# HMS_Olfactometer_v2_0.net
KiCad netlist of a schematic drawn in EAGLE
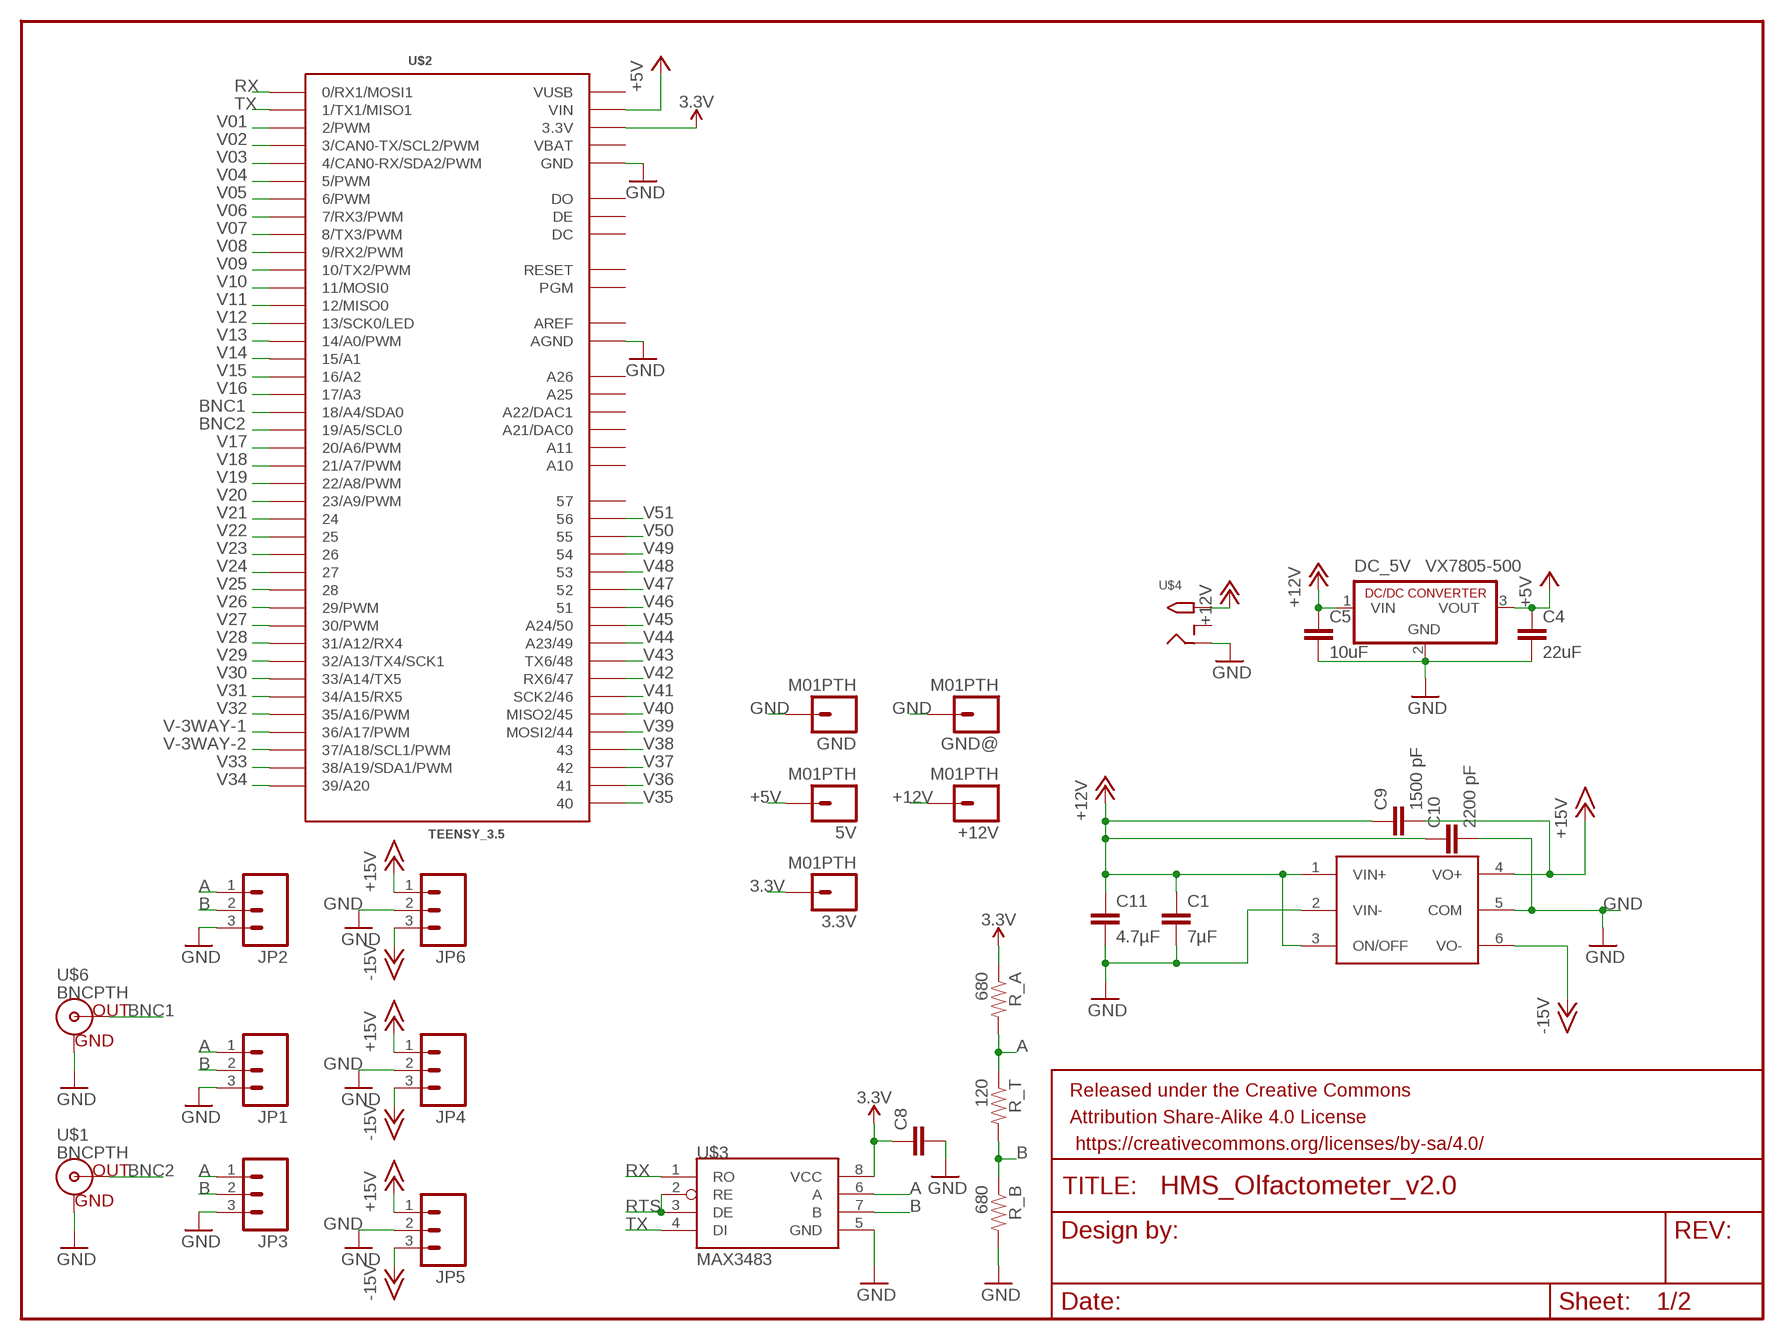
[diagram p0: schematic, sheet 1]
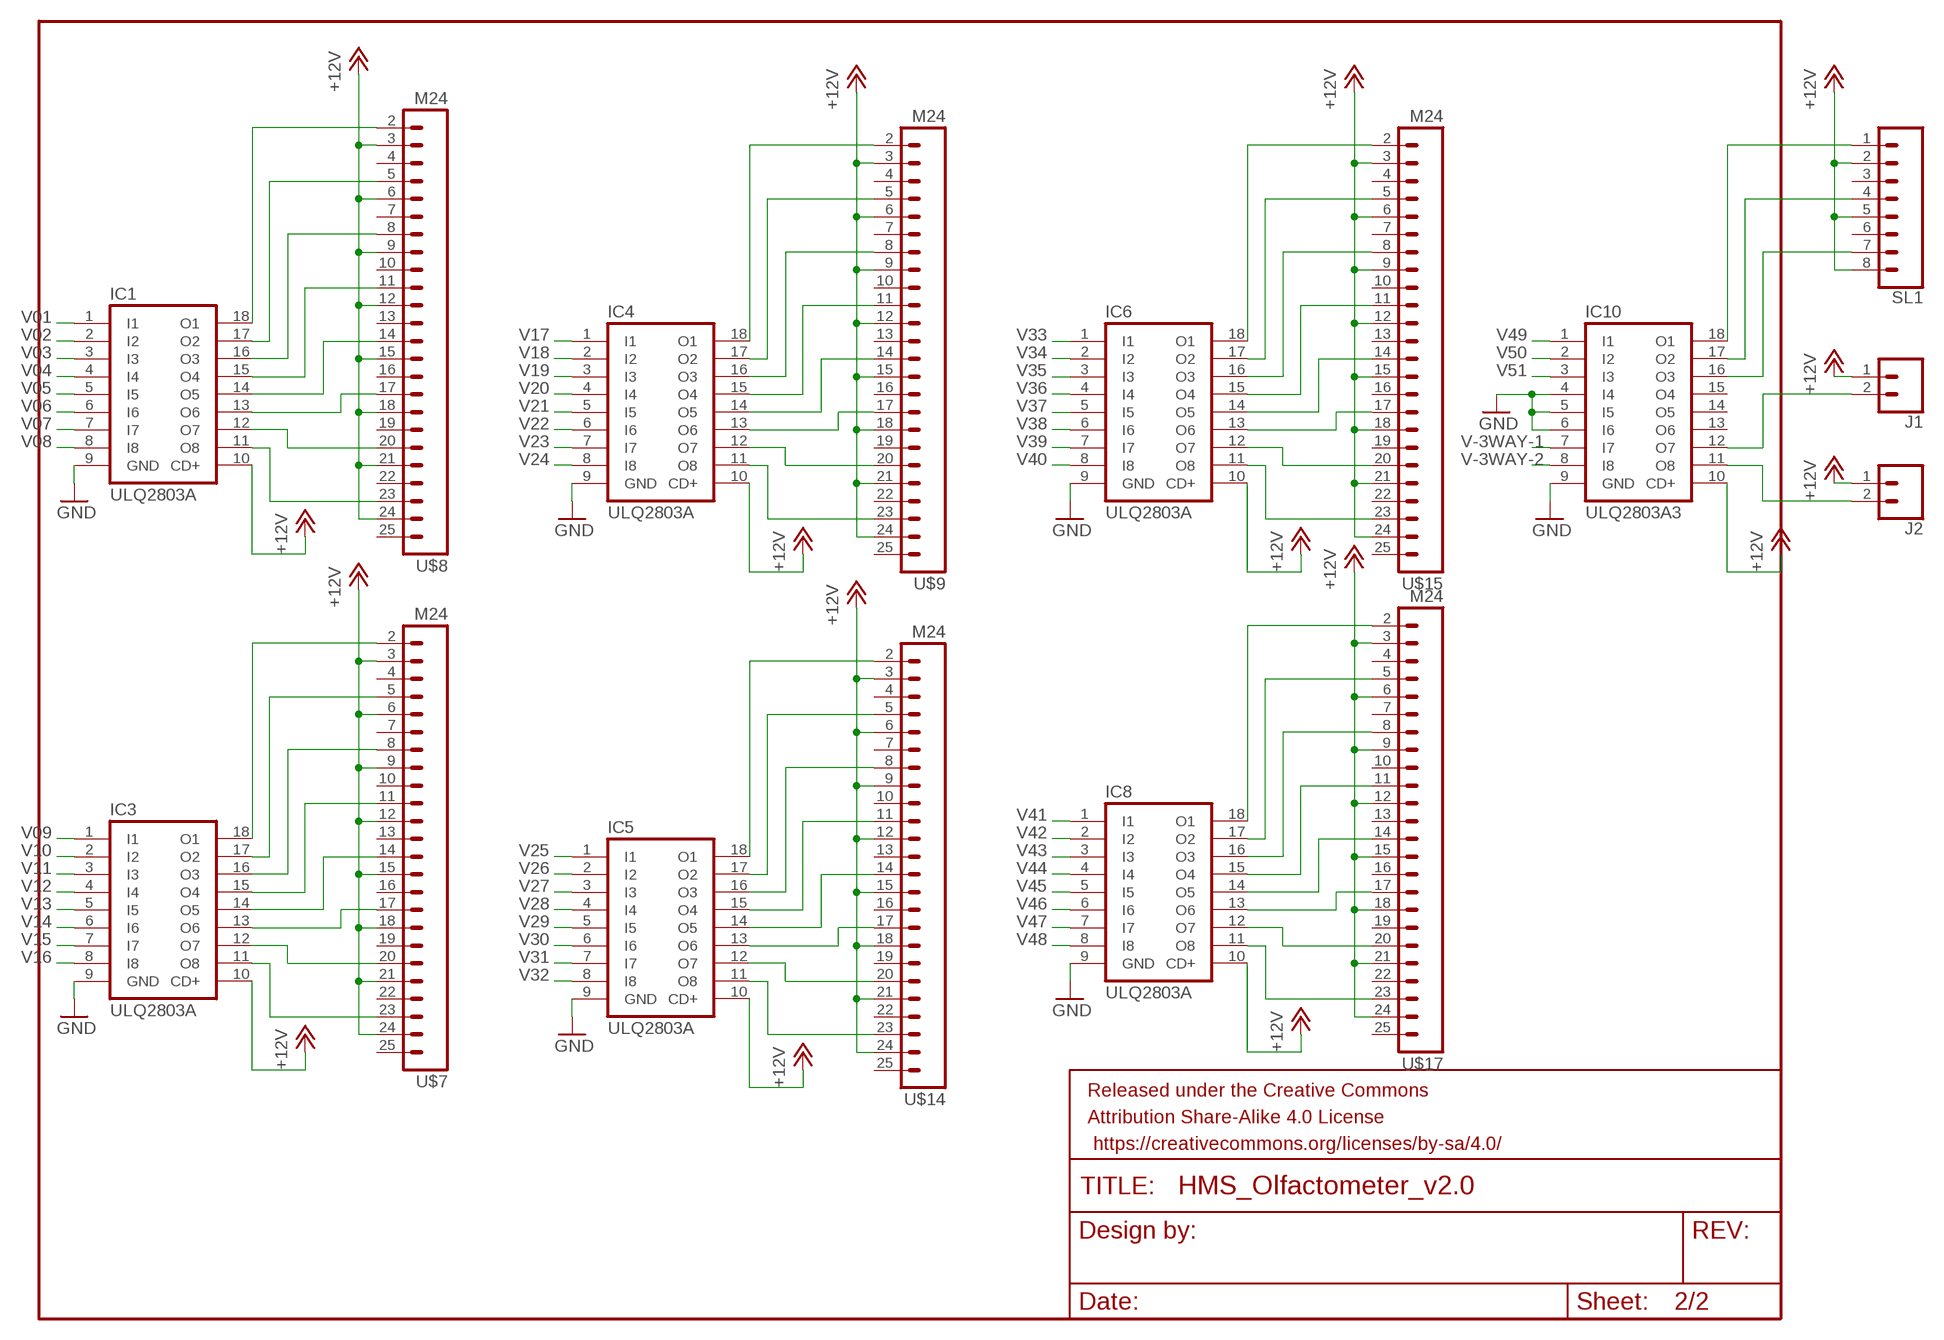
[diagram p1: schematic, sheet 2]

(export (version "E")
  (design (tool "Eeschema 10.0.6"))
  (components
    (comp (ref "+12V")
      (value "M01PTH")
      (footprint "eagle-import:1X01")
      (libsource (lib "eagle-import") (part "M01PTH"))
    )
    (comp (ref "3.3V")
      (value "M01PTH")
      (footprint "eagle-import:1X01")
      (libsource (lib "eagle-import") (part "M01PTH"))
    )
    (comp (ref "5V")
      (value "M01PTH")
      (footprint "eagle-import:1X01")
      (libsource (lib "eagle-import") (part "M01PTH"))
    )
    (comp (ref "C1")
      (value "7µF")
      (footprint "eagle-import:C1812")
      (libsource (lib "eagle-import") (part "C-EUC1812"))
    )
    (comp (ref "C4")
      (value "22uF")
      (footprint "eagle-import:1206")
      (libsource (lib "eagle-import") (part "10UF-6.3V-20%(1206)"))
    )
    (comp (ref "C5")
      (value "10uF")
      (footprint "eagle-import:1206")
      (libsource (lib "eagle-import") (part "CAP1206"))
    )
    (comp (ref "C8")
      (value "CAP1206")
      (footprint "eagle-import:1206")
      (libsource (lib "eagle-import") (part "CAP1206"))
    )
    (comp (ref "C9")
      (value "1500 pF")
      (footprint "eagle-import:C1206")
      (libsource (lib "eagle-import") (part "C-EUC1206"))
    )
    (comp (ref "C10")
      (value "2200 pF")
      (footprint "eagle-import:C1206")
      (libsource (lib "eagle-import") (part "C-EUC1206"))
    )
    (comp (ref "C11")
      (value "4.7µF")
      (footprint "eagle-import:C1812")
      (libsource (lib "eagle-import") (part "C-EUC1812"))
    )
    (comp (ref "DC_+/-15V")
      (value "XPPOWER_+/-15V_60W_DC-DC_SUPPLY")
      (footprint "eagle-import:XPPOWER_60W_JTL60_DC_DC_POWER_SUPPLY")
      (libsource (lib "eagle-import") (part "XPPOWER_+/-15V_60W_DC-DC_SUPPLY"))
    )
    (comp (ref "DC_5V")
      (value "VX7805-500")
      (footprint "eagle-import:SIP3")
      (libsource (lib "eagle-import") (part "R-78C-1.012"))
    )
    (comp (ref "FRAME1")
      (value "FRAME-LETTER")
      (footprint "eagle-import:CREATIVE_COMMONS")
      (libsource (lib "eagle-import") (part "FRAME-LETTER"))
    )
    (comp (ref "GND")
      (value "M01PTH")
      (footprint "eagle-import:1X01")
      (libsource (lib "eagle-import") (part "M01PTH"))
    )
    (comp (ref "GND@")
      (value "M01PTH")
      (footprint "eagle-import:1X01")
      (libsource (lib "eagle-import") (part "M01PTH"))
    )
    (comp (ref "JP1")
      (value "M03POLAR")
      (footprint "eagle-import:MOLEX-1X3")
      (libsource (lib "eagle-import") (part "M03POLAR"))
    )
    (comp (ref "JP2")
      (value "M03POLAR")
      (footprint "eagle-import:MOLEX-1X3")
      (libsource (lib "eagle-import") (part "M03POLAR"))
    )
    (comp (ref "JP3")
      (value "M03POLAR")
      (footprint "eagle-import:MOLEX-1X3")
      (libsource (lib "eagle-import") (part "M03POLAR"))
    )
    (comp (ref "JP4")
      (value "M03SCREW")
      (footprint "eagle-import:SCREWTERMINAL-3.5MM-3")
      (libsource (lib "eagle-import") (part "M03SCREW"))
    )
    (comp (ref "JP5")
      (value "M03SCREW")
      (footprint "eagle-import:SCREWTERMINAL-3.5MM-3")
      (libsource (lib "eagle-import") (part "M03SCREW"))
    )
    (comp (ref "JP6")
      (value "M03SCREW")
      (footprint "eagle-import:SCREWTERMINAL-3.5MM-3")
      (libsource (lib "eagle-import") (part "M03SCREW"))
    )
    (comp (ref "R_A")
      (value "680")
      (footprint "eagle-import:AXIAL-0.5")
      (libsource (lib "eagle-import") (part "RESISTORPTH-1/2W"))
    )
    (comp (ref "R_B")
      (value "680")
      (footprint "eagle-import:AXIAL-0.5")
      (libsource (lib "eagle-import") (part "RESISTORPTH-1/2W"))
    )
    (comp (ref "R_T")
      (value "120")
      (footprint "eagle-import:AXIAL-0.5")
      (libsource (lib "eagle-import") (part "RESISTORPTH-1/2W"))
    )
    (comp (ref "U$1")
      (value "BNCPTH")
      (footprint "eagle-import:BNC")
      (libsource (lib "eagle-import") (part "BNCPTH"))
    )
    (comp (ref "U$2")
      (value "TEENSY_3.5")
      (footprint "eagle-import:TEENSY_3.5_ALL_PINS&PADS")
      (libsource (lib "eagle-import") (part "TEENSY_3.5_ALL_PINS&PADS"))
    )
    (comp (ref "U$3")
      (value "MAX3483")
      (footprint "eagle-import:DIL08")
      (fields (field (name "SPICEPREFIX") "X"))
      (libsource (lib "eagle-import") (part "MAX485DIL"))
    )
    (comp (ref "U$4")
      (value "2.1MMJACKTHM")
      (footprint "eagle-import:PJ-102A")
      (libsource (lib "eagle-import") (part "2.1MMJACKTHM"))
    )
    (comp (ref "U$6")
      (value "BNCPTH")
      (footprint "eagle-import:BNC")
      (libsource (lib "eagle-import") (part "BNCPTH"))
    )
    (comp (ref "FRAME2")
      (value "FRAME-LETTER")
      (footprint "eagle-import:CREATIVE_COMMONS")
      (libsource (lib "eagle-import") (part "FRAME-LETTER"))
    )
    (comp (ref "IC1")
      (value "ULQ2803A")
      (footprint "eagle-import:DIL18")
      (libsource (lib "eagle-import") (part "ULN2803A"))
    )
    (comp (ref "IC3")
      (value "ULQ2803A")
      (footprint "eagle-import:DIL18")
      (libsource (lib "eagle-import") (part "ULN2803A"))
    )
    (comp (ref "IC4")
      (value "ULQ2803A")
      (footprint "eagle-import:DIL18")
      (libsource (lib "eagle-import") (part "ULN2803A"))
    )
    (comp (ref "IC5")
      (value "ULQ2803A")
      (footprint "eagle-import:DIL18")
      (libsource (lib "eagle-import") (part "ULN2803A"))
    )
    (comp (ref "IC6")
      (value "ULQ2803A")
      (footprint "eagle-import:DIL18")
      (libsource (lib "eagle-import") (part "ULN2803A"))
    )
    (comp (ref "IC8")
      (value "ULQ2803A")
      (footprint "eagle-import:DIL18")
      (libsource (lib "eagle-import") (part "ULN2803A"))
    )
    (comp (ref "IC10")
      (value "ULQ2803A3")
      (footprint "eagle-import:DIL18")
      (libsource (lib "eagle-import") (part "ULN2803A"))
    )
    (comp (ref "J1")
      (value "CONN_02")
      (footprint "eagle-import:1X02")
      (libsource (lib "eagle-import") (part "CONN_02"))
    )
    (comp (ref "J2")
      (value "CONN_02")
      (footprint "eagle-import:1X02")
      (libsource (lib "eagle-import") (part "CONN_02"))
    )
    (comp (ref "SL1")
      (value "CONN_08\"")
      (footprint "eagle-import:1X08")
      (libsource (lib "eagle-import") (part "CONN_08{dblquote}"))
    )
    (comp (ref "U$7")
      (value "M24")
      (footprint "eagle-import:1X24")
      (libsource (lib "eagle-import") (part "M24"))
    )
    (comp (ref "U$8")
      (value "M24")
      (footprint "eagle-import:1X24")
      (libsource (lib "eagle-import") (part "M24"))
    )
    (comp (ref "U$9")
      (value "M24")
      (footprint "eagle-import:1X24")
      (libsource (lib "eagle-import") (part "M24"))
    )
    (comp (ref "U$14")
      (value "M24")
      (footprint "eagle-import:1X24")
      (libsource (lib "eagle-import") (part "M24"))
    )
    (comp (ref "U$15")
      (value "M24")
      (footprint "eagle-import:1X24")
      (libsource (lib "eagle-import") (part "M24"))
    )
    (comp (ref "U$17")
      (value "M24")
      (footprint "eagle-import:1X24")
      (libsource (lib "eagle-import") (part "M24"))
    )
  )
  (nets
    (net (code "1") (name "+5V") (class "Default")
      (node (ref "5V") (pin "1") (pinfunction "1_1") (pintype "passive"))
      (node (ref "C4") (pin "1") (pinfunction "1_1") (pintype "passive"))
      (node (ref "DC_5V") (pin "3") (pinfunction "VOUT_3") (pintype "passive"))
      (node (ref "U$2") (pin "VIN") (pinfunction "VIN_VIN") (pintype "power_in"))
    )
    (net (code "2") (name "+12V") (class "Default")
      (node (ref "+12V") (pin "1") (pinfunction "1_1") (pintype "passive"))
      (node (ref "C1") (pin "1") (pinfunction "1_1") (pintype "passive"))
      (node (ref "C10") (pin "1") (pinfunction "1_1") (pintype "passive"))
      (node (ref "C11") (pin "1") (pinfunction "1_1") (pintype "passive"))
      (node (ref "C5") (pin "1") (pinfunction "1_1") (pintype "passive"))
      (node (ref "C9") (pin "1") (pinfunction "1_1") (pintype "passive"))
      (node (ref "DC_+/-15V") (pin "1") (pinfunction "VIN+_1") (pintype "passive"))
      (node (ref "DC_+/-15V") (pin "3") (pinfunction "ON/OFF_3") (pintype "bidirectional"))
      (node (ref "DC_5V") (pin "1") (pinfunction "VIN_1") (pintype "passive"))
      (node (ref "IC1") (pin "10") (pinfunction "CD+_10") (pintype "passive"))
      (node (ref "IC10") (pin "10") (pinfunction "CD+_10") (pintype "passive"))
      (node (ref "IC3") (pin "10") (pinfunction "CD+_10") (pintype "passive"))
      (node (ref "IC4") (pin "10") (pinfunction "CD+_10") (pintype "passive"))
      (node (ref "IC5") (pin "10") (pinfunction "CD+_10") (pintype "passive"))
      (node (ref "IC6") (pin "10") (pinfunction "CD+_10") (pintype "passive"))
      (node (ref "IC8") (pin "10") (pinfunction "CD+_10") (pintype "passive"))
      (node (ref "J1") (pin "1") (pinfunction "1_1") (pintype "passive"))
      (node (ref "J2") (pin "1") (pinfunction "1_1") (pintype "passive"))
      (node (ref "SL1") (pin "2") (pinfunction "2_2") (pintype "passive"))
      (node (ref "SL1") (pin "5") (pinfunction "5_5") (pintype "passive"))
      (node (ref "SL1") (pin "8") (pinfunction "8_8") (pintype "passive"))
      (node (ref "U$14") (pin "12") (pinfunction "12_12") (pintype "passive"))
      (node (ref "U$14") (pin "15") (pinfunction "15_15") (pintype "passive"))
      (node (ref "U$14") (pin "18") (pinfunction "18_18") (pintype "passive"))
      (node (ref "U$14") (pin "21") (pinfunction "21_21") (pintype "passive"))
      (node (ref "U$14") (pin "24") (pinfunction "24_24") (pintype "passive"))
      (node (ref "U$14") (pin "3") (pinfunction "3_3") (pintype "passive"))
      (node (ref "U$14") (pin "6") (pinfunction "6_6") (pintype "passive"))
      (node (ref "U$14") (pin "9") (pinfunction "9_9") (pintype "passive"))
      (node (ref "U$15") (pin "12") (pinfunction "12_12") (pintype "passive"))
      (node (ref "U$15") (pin "15") (pinfunction "15_15") (pintype "passive"))
      (node (ref "U$15") (pin "18") (pinfunction "18_18") (pintype "passive"))
      (node (ref "U$15") (pin "21") (pinfunction "21_21") (pintype "passive"))
      (node (ref "U$15") (pin "24") (pinfunction "24_24") (pintype "passive"))
      (node (ref "U$15") (pin "3") (pinfunction "3_3") (pintype "passive"))
      (node (ref "U$15") (pin "6") (pinfunction "6_6") (pintype "passive"))
      (node (ref "U$15") (pin "9") (pinfunction "9_9") (pintype "passive"))
      (node (ref "U$17") (pin "12") (pinfunction "12_12") (pintype "passive"))
      (node (ref "U$17") (pin "15") (pinfunction "15_15") (pintype "passive"))
      (node (ref "U$17") (pin "18") (pinfunction "18_18") (pintype "passive"))
      (node (ref "U$17") (pin "21") (pinfunction "21_21") (pintype "passive"))
      (node (ref "U$17") (pin "24") (pinfunction "24_24") (pintype "passive"))
      (node (ref "U$17") (pin "3") (pinfunction "3_3") (pintype "passive"))
      (node (ref "U$17") (pin "6") (pinfunction "6_6") (pintype "passive"))
      (node (ref "U$17") (pin "9") (pinfunction "9_9") (pintype "passive"))
      (node (ref "U$4") (pin "TIP") (pinfunction "TIP_TIP") (pintype "bidirectional"))
      (node (ref "U$7") (pin "12") (pinfunction "12_12") (pintype "passive"))
      (node (ref "U$7") (pin "15") (pinfunction "15_15") (pintype "passive"))
      (node (ref "U$7") (pin "18") (pinfunction "18_18") (pintype "passive"))
      (node (ref "U$7") (pin "21") (pinfunction "21_21") (pintype "passive"))
      (node (ref "U$7") (pin "24") (pinfunction "24_24") (pintype "passive"))
      (node (ref "U$7") (pin "3") (pinfunction "3_3") (pintype "passive"))
      (node (ref "U$7") (pin "6") (pinfunction "6_6") (pintype "passive"))
      (node (ref "U$7") (pin "9") (pinfunction "9_9") (pintype "passive"))
      (node (ref "U$8") (pin "12") (pinfunction "12_12") (pintype "passive"))
      (node (ref "U$8") (pin "15") (pinfunction "15_15") (pintype "passive"))
      (node (ref "U$8") (pin "18") (pinfunction "18_18") (pintype "passive"))
      (node (ref "U$8") (pin "21") (pinfunction "21_21") (pintype "passive"))
      (node (ref "U$8") (pin "24") (pinfunction "24_24") (pintype "passive"))
      (node (ref "U$8") (pin "3") (pinfunction "3_3") (pintype "passive"))
      (node (ref "U$8") (pin "6") (pinfunction "6_6") (pintype "passive"))
      (node (ref "U$8") (pin "9") (pinfunction "9_9") (pintype "passive"))
      (node (ref "U$9") (pin "12") (pinfunction "12_12") (pintype "passive"))
      (node (ref "U$9") (pin "15") (pinfunction "15_15") (pintype "passive"))
      (node (ref "U$9") (pin "18") (pinfunction "18_18") (pintype "passive"))
      (node (ref "U$9") (pin "21") (pinfunction "21_21") (pintype "passive"))
      (node (ref "U$9") (pin "24") (pinfunction "24_24") (pintype "passive"))
      (node (ref "U$9") (pin "3") (pinfunction "3_3") (pintype "passive"))
      (node (ref "U$9") (pin "6") (pinfunction "6_6") (pintype "passive"))
      (node (ref "U$9") (pin "9") (pinfunction "9_9") (pintype "passive"))
    )
    (net (code "3") (name "+15V") (class "Default")
      (node (ref "C9") (pin "2") (pinfunction "2_2") (pintype "passive"))
      (node (ref "DC_+/-15V") (pin "4") (pinfunction "VO+_4") (pintype "power_in"))
      (node (ref "JP4") (pin "1") (pinfunction "1_1") (pintype "passive"))
      (node (ref "JP5") (pin "1") (pinfunction "1_1") (pintype "passive"))
      (node (ref "JP6") (pin "1") (pinfunction "1_1") (pintype "passive"))
    )
    (net (code "4") (name "-15V") (class "Default")
      (node (ref "DC_+/-15V") (pin "6") (pinfunction "VO-_6") (pintype "power_in"))
      (node (ref "JP4") (pin "3") (pinfunction "3_3") (pintype "passive"))
      (node (ref "JP5") (pin "3") (pinfunction "3_3") (pintype "passive"))
      (node (ref "JP6") (pin "3") (pinfunction "3_3") (pintype "passive"))
    )
    (net (code "5") (name "3.3V") (class "Default")
      (node (ref "3.3V") (pin "1") (pinfunction "1_1") (pintype "passive"))
      (node (ref "C8") (pin "1") (pinfunction "1_1") (pintype "passive"))
      (node (ref "R_A") (pin "P$1") (pinfunction "1_P$1") (pintype "passive"))
      (node (ref "U$2") (pin "3.3V") (pinfunction "3.3V_3.3V") (pintype "power_in"))
      (node (ref "U$2") (pin "3.3V2") (pinfunction "3.3V_3.3V2") (pintype "power_in"))
      (node (ref "U$2") (pin "3.3V3") (pinfunction "3.3V_3.3V3") (pintype "power_in"))
      (node (ref "U$2") (pin "3.3V4") (pinfunction "3.3V_3.3V4") (pintype "power_in"))
      (node (ref "U$3") (pin "8") (pinfunction "VCC_8") (pintype "bidirectional"))
    )
    (net (code "6") (name "A") (class "Default")
      (node (ref "JP1") (pin "1") (pinfunction "1_1") (pintype "passive"))
      (node (ref "JP2") (pin "1") (pinfunction "1_1") (pintype "passive"))
      (node (ref "JP3") (pin "1") (pinfunction "1_1") (pintype "passive"))
      (node (ref "R_A") (pin "P$2") (pinfunction "2_P$2") (pintype "passive"))
      (node (ref "R_T") (pin "P$1") (pinfunction "1_P$1") (pintype "passive"))
      (node (ref "U$3") (pin "6") (pinfunction "A_6") (pintype "bidirectional"))
    )
    (net (code "7") (name "AREF") (class "Default")
      (node (ref "U$2") (pin "AREF") (pinfunction "AREF_AREF") (pintype "power_in"))
    )
    (net (code "8") (name "B") (class "Default")
      (node (ref "JP1") (pin "2") (pinfunction "2_2") (pintype "passive"))
      (node (ref "JP2") (pin "2") (pinfunction "2_2") (pintype "passive"))
      (node (ref "JP3") (pin "2") (pinfunction "2_2") (pintype "passive"))
      (node (ref "R_B") (pin "P$1") (pinfunction "1_P$1") (pintype "passive"))
      (node (ref "R_T") (pin "P$2") (pinfunction "2_P$2") (pintype "passive"))
      (node (ref "U$3") (pin "7") (pinfunction "B_7") (pintype "bidirectional"))
    )
    (net (code "9") (name "BNC1") (class "Default")
      (node (ref "U$2") (pin "18/A4") (pinfunction "18/A4/SDA0_18/A4") (pintype "bidirectional"))
      (node (ref "U$6") (pin "S") (pinfunction "OUT_S") (pintype "bidirectional"))
    )
    (net (code "10") (name "BNC2") (class "Default")
      (node (ref "U$1") (pin "S") (pinfunction "OUT_S") (pintype "bidirectional"))
      (node (ref "U$2") (pin "19/A5") (pinfunction "19/A5/SCL0_19/A5") (pintype "bidirectional"))
    )
    (net (code "11") (name "GND") (class "Default")
      (node (ref "C1") (pin "2") (pinfunction "2_2") (pintype "passive"))
      (node (ref "C10") (pin "2") (pinfunction "2_2") (pintype "passive"))
      (node (ref "C11") (pin "2") (pinfunction "2_2") (pintype "passive"))
      (node (ref "C4") (pin "2") (pinfunction "2_2") (pintype "passive"))
      (node (ref "C5") (pin "2") (pinfunction "2_2") (pintype "passive"))
      (node (ref "C8") (pin "2") (pinfunction "2_2") (pintype "passive"))
      (node (ref "DC_+/-15V") (pin "2") (pinfunction "VIN-_2") (pintype "power_in"))
      (node (ref "DC_+/-15V") (pin "5") (pinfunction "COM_5") (pintype "power_in"))
      (node (ref "DC_5V") (pin "2") (pinfunction "GND_2") (pintype "passive"))
      (node (ref "GND") (pin "1") (pinfunction "1_1") (pintype "passive"))
      (node (ref "GND@") (pin "1") (pinfunction "1_1") (pintype "passive"))
      (node (ref "IC1") (pin "9") (pinfunction "GND_9") (pintype "power_in"))
      (node (ref "IC10") (pin "4") (pinfunction "I4_4") (pintype "input"))
      (node (ref "IC10") (pin "5") (pinfunction "I5_5") (pintype "input"))
      (node (ref "IC10") (pin "6") (pinfunction "I6_6") (pintype "input"))
      (node (ref "IC10") (pin "9") (pinfunction "GND_9") (pintype "power_in"))
      (node (ref "IC3") (pin "9") (pinfunction "GND_9") (pintype "power_in"))
      (node (ref "IC4") (pin "9") (pinfunction "GND_9") (pintype "power_in"))
      (node (ref "IC5") (pin "9") (pinfunction "GND_9") (pintype "power_in"))
      (node (ref "IC6") (pin "9") (pinfunction "GND_9") (pintype "power_in"))
      (node (ref "IC8") (pin "9") (pinfunction "GND_9") (pintype "power_in"))
      (node (ref "JP1") (pin "3") (pinfunction "3_3") (pintype "passive"))
      (node (ref "JP2") (pin "3") (pinfunction "3_3") (pintype "passive"))
      (node (ref "JP3") (pin "3") (pinfunction "3_3") (pintype "passive"))
      (node (ref "JP4") (pin "2") (pinfunction "2_2") (pintype "passive"))
      (node (ref "JP5") (pin "2") (pinfunction "2_2") (pintype "passive"))
      (node (ref "JP6") (pin "2") (pinfunction "2_2") (pintype "passive"))
      (node (ref "R_B") (pin "P$2") (pinfunction "2_P$2") (pintype "passive"))
      (node (ref "U$1") (pin "GND") (pinfunction "GND_GND") (pintype "bidirectional"))
      (node (ref "U$2") (pin "AGND") (pinfunction "AGND_AGND") (pintype "power_in"))
      (node (ref "U$2") (pin "GND") (pinfunction "GND_GND") (pintype "power_in"))
      (node (ref "U$2") (pin "GND1") (pinfunction "GND_GND1") (pintype "power_in"))
      (node (ref "U$2") (pin "GND2") (pinfunction "GND_GND2") (pintype "power_in"))
      (node (ref "U$2") (pin "GND3") (pinfunction "GND_GND3") (pintype "power_in"))
      (node (ref "U$2") (pin "GND4") (pinfunction "GND_GND4") (pintype "power_in"))
      (node (ref "U$2") (pin "GND5") (pinfunction "GND_GND5") (pintype "power_in"))
      (node (ref "U$2") (pin "GND6") (pinfunction "GND_GND6") (pintype "power_in"))
      (node (ref "U$3") (pin "5") (pinfunction "GND_5") (pintype "bidirectional"))
      (node (ref "U$4") (pin "RING") (pinfunction "RING_RING") (pintype "bidirectional"))
      (node (ref "U$6") (pin "GND") (pinfunction "GND_GND") (pintype "bidirectional"))
    )
    (net (code "12") (name "Net-(IC1-O1)") (class "Default")
      (node (ref "IC1") (pin "18") (pinfunction "O1_18") (pintype "open_collector"))
      (node (ref "U$8") (pin "2") (pinfunction "2_2") (pintype "passive"))
    )
    (net (code "13") (name "Net-(IC1-O2)") (class "Default")
      (node (ref "IC1") (pin "17") (pinfunction "O2_17") (pintype "open_collector"))
      (node (ref "U$8") (pin "5") (pinfunction "5_5") (pintype "passive"))
    )
    (net (code "14") (name "Net-(IC1-O3)") (class "Default")
      (node (ref "IC1") (pin "16") (pinfunction "O3_16") (pintype "open_collector"))
      (node (ref "U$8") (pin "8") (pinfunction "8_8") (pintype "passive"))
    )
    (net (code "15") (name "Net-(IC1-O4)") (class "Default")
      (node (ref "IC1") (pin "15") (pinfunction "O4_15") (pintype "open_collector"))
      (node (ref "U$8") (pin "11") (pinfunction "11_11") (pintype "passive"))
    )
    (net (code "16") (name "Net-(IC1-O5)") (class "Default")
      (node (ref "IC1") (pin "14") (pinfunction "O5_14") (pintype "open_collector"))
      (node (ref "U$8") (pin "14") (pinfunction "14_14") (pintype "passive"))
    )
    (net (code "17") (name "Net-(IC1-O6)") (class "Default")
      (node (ref "IC1") (pin "13") (pinfunction "O6_13") (pintype "open_collector"))
      (node (ref "U$8") (pin "17") (pinfunction "17_17") (pintype "passive"))
    )
    (net (code "18") (name "Net-(IC1-O7)") (class "Default")
      (node (ref "IC1") (pin "12") (pinfunction "O7_12") (pintype "open_collector"))
      (node (ref "U$8") (pin "20") (pinfunction "20_20") (pintype "passive"))
    )
    (net (code "19") (name "Net-(IC1-O8)") (class "Default")
      (node (ref "IC1") (pin "11") (pinfunction "O8_11") (pintype "open_collector"))
      (node (ref "U$8") (pin "23") (pinfunction "23_23") (pintype "passive"))
    )
    (net (code "20") (name "Net-(IC3-O1)") (class "Default")
      (node (ref "IC3") (pin "18") (pinfunction "O1_18") (pintype "open_collector"))
      (node (ref "U$7") (pin "2") (pinfunction "2_2") (pintype "passive"))
    )
    (net (code "21") (name "Net-(IC3-O2)") (class "Default")
      (node (ref "IC3") (pin "17") (pinfunction "O2_17") (pintype "open_collector"))
      (node (ref "U$7") (pin "5") (pinfunction "5_5") (pintype "passive"))
    )
    (net (code "22") (name "Net-(IC3-O3)") (class "Default")
      (node (ref "IC3") (pin "16") (pinfunction "O3_16") (pintype "open_collector"))
      (node (ref "U$7") (pin "8") (pinfunction "8_8") (pintype "passive"))
    )
    (net (code "23") (name "Net-(IC3-O4)") (class "Default")
      (node (ref "IC3") (pin "15") (pinfunction "O4_15") (pintype "open_collector"))
      (node (ref "U$7") (pin "11") (pinfunction "11_11") (pintype "passive"))
    )
    (net (code "24") (name "Net-(IC3-O5)") (class "Default")
      (node (ref "IC3") (pin "14") (pinfunction "O5_14") (pintype "open_collector"))
      (node (ref "U$7") (pin "14") (pinfunction "14_14") (pintype "passive"))
    )
    (net (code "25") (name "Net-(IC3-O6)") (class "Default")
      (node (ref "IC3") (pin "13") (pinfunction "O6_13") (pintype "open_collector"))
      (node (ref "U$7") (pin "17") (pinfunction "17_17") (pintype "passive"))
    )
    (net (code "26") (name "Net-(IC3-O7)") (class "Default")
      (node (ref "IC3") (pin "12") (pinfunction "O7_12") (pintype "open_collector"))
      (node (ref "U$7") (pin "20") (pinfunction "20_20") (pintype "passive"))
    )
    (net (code "27") (name "Net-(IC3-O8)") (class "Default")
      (node (ref "IC3") (pin "11") (pinfunction "O8_11") (pintype "open_collector"))
      (node (ref "U$7") (pin "23") (pinfunction "23_23") (pintype "passive"))
    )
    (net (code "28") (name "Net-(IC4-O1)") (class "Default")
      (node (ref "IC4") (pin "18") (pinfunction "O1_18") (pintype "open_collector"))
      (node (ref "U$9") (pin "2") (pinfunction "2_2") (pintype "passive"))
    )
    (net (code "29") (name "Net-(IC4-O2)") (class "Default")
      (node (ref "IC4") (pin "17") (pinfunction "O2_17") (pintype "open_collector"))
      (node (ref "U$9") (pin "5") (pinfunction "5_5") (pintype "passive"))
    )
    (net (code "30") (name "Net-(IC4-O3)") (class "Default")
      (node (ref "IC4") (pin "16") (pinfunction "O3_16") (pintype "open_collector"))
      (node (ref "U$9") (pin "8") (pinfunction "8_8") (pintype "passive"))
    )
    (net (code "31") (name "Net-(IC4-O4)") (class "Default")
      (node (ref "IC4") (pin "15") (pinfunction "O4_15") (pintype "open_collector"))
      (node (ref "U$9") (pin "11") (pinfunction "11_11") (pintype "passive"))
    )
    (net (code "32") (name "Net-(IC4-O5)") (class "Default")
      (node (ref "IC4") (pin "14") (pinfunction "O5_14") (pintype "open_collector"))
      (node (ref "U$9") (pin "14") (pinfunction "14_14") (pintype "passive"))
    )
    (net (code "33") (name "Net-(IC4-O6)") (class "Default")
      (node (ref "IC4") (pin "13") (pinfunction "O6_13") (pintype "open_collector"))
      (node (ref "U$9") (pin "17") (pinfunction "17_17") (pintype "passive"))
    )
    (net (code "34") (name "Net-(IC4-O7)") (class "Default")
      (node (ref "IC4") (pin "12") (pinfunction "O7_12") (pintype "open_collector"))
      (node (ref "U$9") (pin "20") (pinfunction "20_20") (pintype "passive"))
    )
    (net (code "35") (name "Net-(IC4-O8)") (class "Default")
      (node (ref "IC4") (pin "11") (pinfunction "O8_11") (pintype "open_collector"))
      (node (ref "U$9") (pin "23") (pinfunction "23_23") (pintype "passive"))
    )
    (net (code "36") (name "Net-(IC5-O1)") (class "Default")
      (node (ref "IC5") (pin "18") (pinfunction "O1_18") (pintype "open_collector"))
      (node (ref "U$14") (pin "2") (pinfunction "2_2") (pintype "passive"))
    )
    (net (code "37") (name "Net-(IC5-O2)") (class "Default")
      (node (ref "IC5") (pin "17") (pinfunction "O2_17") (pintype "open_collector"))
      (node (ref "U$14") (pin "5") (pinfunction "5_5") (pintype "passive"))
    )
    (net (code "38") (name "Net-(IC5-O3)") (class "Default")
      (node (ref "IC5") (pin "16") (pinfunction "O3_16") (pintype "open_collector"))
      (node (ref "U$14") (pin "8") (pinfunction "8_8") (pintype "passive"))
    )
    (net (code "39") (name "Net-(IC5-O4)") (class "Default")
      (node (ref "IC5") (pin "15") (pinfunction "O4_15") (pintype "open_collector"))
      (node (ref "U$14") (pin "11") (pinfunction "11_11") (pintype "passive"))
    )
    (net (code "40") (name "Net-(IC5-O5)") (class "Default")
      (node (ref "IC5") (pin "14") (pinfunction "O5_14") (pintype "open_collector"))
      (node (ref "U$14") (pin "14") (pinfunction "14_14") (pintype "passive"))
    )
    (net (code "41") (name "Net-(IC5-O6)") (class "Default")
      (node (ref "IC5") (pin "13") (pinfunction "O6_13") (pintype "open_collector"))
      (node (ref "U$14") (pin "17") (pinfunction "17_17") (pintype "passive"))
    )
    (net (code "42") (name "Net-(IC5-O7)") (class "Default")
      (node (ref "IC5") (pin "12") (pinfunction "O7_12") (pintype "open_collector"))
      (node (ref "U$14") (pin "20") (pinfunction "20_20") (pintype "passive"))
    )
    (net (code "43") (name "Net-(IC5-O8)") (class "Default")
      (node (ref "IC5") (pin "11") (pinfunction "O8_11") (pintype "open_collector"))
      (node (ref "U$14") (pin "23") (pinfunction "23_23") (pintype "passive"))
    )
    (net (code "44") (name "Net-(IC6-O1)") (class "Default")
      (node (ref "IC6") (pin "18") (pinfunction "O1_18") (pintype "open_collector"))
      (node (ref "U$15") (pin "2") (pinfunction "2_2") (pintype "passive"))
    )
    (net (code "45") (name "Net-(IC6-O2)") (class "Default")
      (node (ref "IC6") (pin "17") (pinfunction "O2_17") (pintype "open_collector"))
      (node (ref "U$15") (pin "5") (pinfunction "5_5") (pintype "passive"))
    )
    (net (code "46") (name "Net-(IC6-O3)") (class "Default")
      (node (ref "IC6") (pin "16") (pinfunction "O3_16") (pintype "open_collector"))
      (node (ref "U$15") (pin "8") (pinfunction "8_8") (pintype "passive"))
    )
    (net (code "47") (name "Net-(IC6-O4)") (class "Default")
      (node (ref "IC6") (pin "15") (pinfunction "O4_15") (pintype "open_collector"))
      (node (ref "U$15") (pin "11") (pinfunction "11_11") (pintype "passive"))
    )
    (net (code "48") (name "Net-(IC6-O5)") (class "Default")
      (node (ref "IC6") (pin "14") (pinfunction "O5_14") (pintype "open_collector"))
      (node (ref "U$15") (pin "14") (pinfunction "14_14") (pintype "passive"))
    )
    (net (code "49") (name "Net-(IC6-O6)") (class "Default")
      (node (ref "IC6") (pin "13") (pinfunction "O6_13") (pintype "open_collector"))
      (node (ref "U$15") (pin "17") (pinfunction "17_17") (pintype "passive"))
    )
    (net (code "50") (name "Net-(IC6-O7)") (class "Default")
      (node (ref "IC6") (pin "12") (pinfunction "O7_12") (pintype "open_collector"))
      (node (ref "U$15") (pin "20") (pinfunction "20_20") (pintype "passive"))
    )
    (net (code "51") (name "Net-(IC6-O8)") (class "Default")
      (node (ref "IC6") (pin "11") (pinfunction "O8_11") (pintype "open_collector"))
      (node (ref "U$15") (pin "23") (pinfunction "23_23") (pintype "passive"))
    )
    (net (code "52") (name "Net-(IC8-O1)") (class "Default")
      (node (ref "IC8") (pin "18") (pinfunction "O1_18") (pintype "open_collector"))
      (node (ref "U$17") (pin "2") (pinfunction "2_2") (pintype "passive"))
    )
    (net (code "53") (name "Net-(IC8-O2)") (class "Default")
      (node (ref "IC8") (pin "17") (pinfunction "O2_17") (pintype "open_collector"))
      (node (ref "U$17") (pin "5") (pinfunction "5_5") (pintype "passive"))
    )
    (net (code "54") (name "Net-(IC8-O3)") (class "Default")
      (node (ref "IC8") (pin "16") (pinfunction "O3_16") (pintype "open_collector"))
      (node (ref "U$17") (pin "8") (pinfunction "8_8") (pintype "passive"))
    )
    (net (code "55") (name "Net-(IC8-O4)") (class "Default")
      (node (ref "IC8") (pin "15") (pinfunction "O4_15") (pintype "open_collector"))
      (node (ref "U$17") (pin "11") (pinfunction "11_11") (pintype "passive"))
    )
    (net (code "56") (name "Net-(IC8-O5)") (class "Default")
      (node (ref "IC8") (pin "14") (pinfunction "O5_14") (pintype "open_collector"))
      (node (ref "U$17") (pin "14") (pinfunction "14_14") (pintype "passive"))
    )
    (net (code "57") (name "Net-(IC8-O6)") (class "Default")
      (node (ref "IC8") (pin "13") (pinfunction "O6_13") (pintype "open_collector"))
      (node (ref "U$17") (pin "17") (pinfunction "17_17") (pintype "passive"))
    )
    (net (code "58") (name "Net-(IC8-O7)") (class "Default")
      (node (ref "IC8") (pin "12") (pinfunction "O7_12") (pintype "open_collector"))
      (node (ref "U$17") (pin "20") (pinfunction "20_20") (pintype "passive"))
    )
    (net (code "59") (name "Net-(IC8-O8)") (class "Default")
      (node (ref "IC8") (pin "11") (pinfunction "O8_11") (pintype "open_collector"))
      (node (ref "U$17") (pin "23") (pinfunction "23_23") (pintype "passive"))
    )
    (net (code "60") (name "Net-(IC10-O1)") (class "Default")
      (node (ref "IC10") (pin "18") (pinfunction "O1_18") (pintype "open_collector"))
      (node (ref "SL1") (pin "1") (pinfunction "1_1") (pintype "passive"))
    )
    (net (code "61") (name "Net-(IC10-O2)") (class "Default")
      (node (ref "IC10") (pin "17") (pinfunction "O2_17") (pintype "open_collector"))
      (node (ref "SL1") (pin "4") (pinfunction "4_4") (pintype "passive"))
    )
    (net (code "62") (name "Net-(IC10-O3)") (class "Default")
      (node (ref "IC10") (pin "16") (pinfunction "O3_16") (pintype "open_collector"))
      (node (ref "SL1") (pin "7") (pinfunction "7_7") (pintype "passive"))
    )
    (net (code "63") (name "Net-(IC10-O7)") (class "Default")
      (node (ref "IC10") (pin "12") (pinfunction "O7_12") (pintype "open_collector"))
      (node (ref "J1") (pin "2") (pinfunction "2_2") (pintype "passive"))
    )
    (net (code "64") (name "Net-(IC10-O8)") (class "Default")
      (node (ref "IC10") (pin "11") (pinfunction "O8_11") (pintype "open_collector"))
      (node (ref "J2") (pin "2") (pinfunction "2_2") (pintype "passive"))
    )
    (net (code "65") (name "RTS") (class "Default")
      (node (ref "U$3") (pin "2") (pinfunction "RE_2") (pintype "bidirectional"))
      (node (ref "U$3") (pin "3") (pinfunction "DE_3") (pintype "bidirectional"))
    )
    (net (code "66") (name "RX") (class "Default")
      (node (ref "U$2") (pin "0") (pinfunction "0/RX1/MOSI1_0") (pintype "bidirectional"))
      (node (ref "U$3") (pin "1") (pinfunction "RO_1") (pintype "bidirectional"))
    )
    (net (code "67") (name "TX") (class "Default")
      (node (ref "U$2") (pin "1") (pinfunction "1/TX1/MISO1_1") (pintype "bidirectional"))
      (node (ref "U$3") (pin "4") (pinfunction "DI_4") (pintype "bidirectional"))
    )
    (net (code "68") (name "V-3WAY-1") (class "Default")
      (node (ref "IC10") (pin "7") (pinfunction "I7_7") (pintype "input"))
      (node (ref "U$2") (pin "36/A17") (pinfunction "36/A17/PWM_36/A17") (pintype "bidirectional"))
    )
    (net (code "69") (name "V-3WAY-2") (class "Default")
      (node (ref "IC10") (pin "8") (pinfunction "I8_8") (pintype "input"))
      (node (ref "U$2") (pin "37/A18") (pinfunction "37/A18/SCL1/PWM_37/A18") (pintype "bidirectional"))
    )
    (net (code "70") (name "V01") (class "Default")
      (node (ref "IC1") (pin "1") (pinfunction "I1_1") (pintype "input"))
      (node (ref "U$2") (pin "2") (pinfunction "2/PWM_2") (pintype "bidirectional"))
    )
    (net (code "71") (name "V02") (class "Default")
      (node (ref "IC1") (pin "2") (pinfunction "I2_2") (pintype "input"))
      (node (ref "U$2") (pin "3") (pinfunction "3/CAN0-TX/SCL2/PWM_3") (pintype "bidirectional"))
    )
    (net (code "72") (name "V03") (class "Default")
      (node (ref "IC1") (pin "3") (pinfunction "I3_3") (pintype "input"))
      (node (ref "U$2") (pin "4") (pinfunction "4/CAN0-RX/SDA2/PWM_4") (pintype "bidirectional"))
    )
    (net (code "73") (name "V04") (class "Default")
      (node (ref "IC1") (pin "4") (pinfunction "I4_4") (pintype "input"))
      (node (ref "U$2") (pin "5") (pinfunction "5/PWM_5") (pintype "bidirectional"))
    )
    (net (code "74") (name "V05") (class "Default")
      (node (ref "IC1") (pin "5") (pinfunction "I5_5") (pintype "input"))
      (node (ref "U$2") (pin "6") (pinfunction "6/PWM_6") (pintype "bidirectional"))
    )
    (net (code "75") (name "V06") (class "Default")
      (node (ref "IC1") (pin "6") (pinfunction "I6_6") (pintype "input"))
      (node (ref "U$2") (pin "7") (pinfunction "7/RX3/PWM_7") (pintype "bidirectional"))
    )
    (net (code "76") (name "V07") (class "Default")
      (node (ref "IC1") (pin "7") (pinfunction "I7_7") (pintype "input"))
      (node (ref "U$2") (pin "8") (pinfunction "8/TX3/PWM_8") (pintype "bidirectional"))
    )
    (net (code "77") (name "V08") (class "Default")
      (node (ref "IC1") (pin "8") (pinfunction "I8_8") (pintype "input"))
      (node (ref "U$2") (pin "9") (pinfunction "9/RX2/PWM_9") (pintype "bidirectional"))
    )
    (net (code "78") (name "V09") (class "Default")
      (node (ref "IC3") (pin "1") (pinfunction "I1_1") (pintype "input"))
      (node (ref "U$2") (pin "10") (pinfunction "10/TX2/PWM_10") (pintype "bidirectional"))
    )
    (net (code "79") (name "V10") (class "Default")
      (node (ref "IC3") (pin "2") (pinfunction "I2_2") (pintype "input"))
      (node (ref "U$2") (pin "11") (pinfunction "11/MOSI0_11") (pintype "bidirectional"))
    )
    (net (code "80") (name "V11") (class "Default")
      (node (ref "IC3") (pin "3") (pinfunction "I3_3") (pintype "input"))
      (node (ref "U$2") (pin "12") (pinfunction "12/MISO0_12") (pintype "bidirectional"))
    )
    (net (code "81") (name "V12") (class "Default")
      (node (ref "IC3") (pin "4") (pinfunction "I4_4") (pintype "input"))
      (node (ref "U$2") (pin "13") (pinfunction "13/SCK0/LED_13") (pintype "bidirectional"))
    )
    (net (code "82") (name "V13") (class "Default")
      (node (ref "IC3") (pin "5") (pinfunction "I5_5") (pintype "input"))
      (node (ref "U$2") (pin "14/A0") (pinfunction "14/A0/PWM_14/A0") (pintype "bidirectional"))
    )
    (net (code "83") (name "V14") (class "Default")
      (node (ref "IC3") (pin "6") (pinfunction "I6_6") (pintype "input"))
      (node (ref "U$2") (pin "15/A1") (pinfunction "15/A1_15/A1") (pintype "bidirectional"))
    )
    (net (code "84") (name "V15") (class "Default")
      (node (ref "IC3") (pin "7") (pinfunction "I7_7") (pintype "input"))
      (node (ref "U$2") (pin "16/A2") (pinfunction "16/A2_16/A2") (pintype "bidirectional"))
    )
    (net (code "85") (name "V16") (class "Default")
      (node (ref "IC3") (pin "8") (pinfunction "I8_8") (pintype "input"))
      (node (ref "U$2") (pin "17/A3") (pinfunction "17/A3_17/A3") (pintype "bidirectional"))
    )
    (net (code "86") (name "V17") (class "Default")
      (node (ref "IC4") (pin "1") (pinfunction "I1_1") (pintype "input"))
      (node (ref "U$2") (pin "20/A6") (pinfunction "20/A6/PWM_20/A6") (pintype "bidirectional"))
    )
    (net (code "87") (name "V18") (class "Default")
      (node (ref "IC4") (pin "2") (pinfunction "I2_2") (pintype "input"))
      (node (ref "U$2") (pin "21/A7") (pinfunction "21/A7/PWM_21/A7") (pintype "bidirectional"))
    )
    (net (code "88") (name "V19") (class "Default")
      (node (ref "IC4") (pin "3") (pinfunction "I3_3") (pintype "input"))
      (node (ref "U$2") (pin "22/A8") (pinfunction "22/A8/PWM_22/A8") (pintype "bidirectional"))
    )
    (net (code "89") (name "V20") (class "Default")
      (node (ref "IC4") (pin "4") (pinfunction "I4_4") (pintype "input"))
      (node (ref "U$2") (pin "23/A9") (pinfunction "23/A9/PWM_23/A9") (pintype "bidirectional"))
    )
    (net (code "90") (name "V21") (class "Default")
      (node (ref "IC4") (pin "5") (pinfunction "I5_5") (pintype "input"))
      (node (ref "U$2") (pin "24") (pinfunction "24_24") (pintype "bidirectional"))
    )
    (net (code "91") (name "V22") (class "Default")
      (node (ref "IC4") (pin "6") (pinfunction "I6_6") (pintype "input"))
      (node (ref "U$2") (pin "25") (pinfunction "25_25") (pintype "bidirectional"))
    )
    (net (code "92") (name "V23") (class "Default")
      (node (ref "IC4") (pin "7") (pinfunction "I7_7") (pintype "input"))
      (node (ref "U$2") (pin "26") (pinfunction "26_26") (pintype "bidirectional"))
    )
    (net (code "93") (name "V24") (class "Default")
      (node (ref "IC4") (pin "8") (pinfunction "I8_8") (pintype "input"))
      (node (ref "U$2") (pin "27") (pinfunction "27_27") (pintype "bidirectional"))
    )
    (net (code "94") (name "V25") (class "Default")
      (node (ref "IC5") (pin "1") (pinfunction "I1_1") (pintype "input"))
      (node (ref "U$2") (pin "28") (pinfunction "28_28") (pintype "bidirectional"))
    )
    (net (code "95") (name "V26") (class "Default")
      (node (ref "IC5") (pin "2") (pinfunction "I2_2") (pintype "input"))
      (node (ref "U$2") (pin "29") (pinfunction "29/PWM_29") (pintype "bidirectional"))
    )
    (net (code "96") (name "V27") (class "Default")
      (node (ref "IC5") (pin "3") (pinfunction "I3_3") (pintype "input"))
      (node (ref "U$2") (pin "30") (pinfunction "30/PWM_30") (pintype "bidirectional"))
    )
    (net (code "97") (name "V28") (class "Default")
      (node (ref "IC5") (pin "4") (pinfunction "I4_4") (pintype "input"))
      (node (ref "U$2") (pin "31/A12") (pinfunction "31/A12/RX4_31/A12") (pintype "bidirectional"))
    )
    (net (code "98") (name "V29") (class "Default")
      (node (ref "IC5") (pin "5") (pinfunction "I5_5") (pintype "input"))
      (node (ref "U$2") (pin "32/A13") (pinfunction "32/A13/TX4/SCK1_32/A13") (pintype "bidirectional"))
    )
    (net (code "99") (name "V30") (class "Default")
      (node (ref "IC5") (pin "6") (pinfunction "I6_6") (pintype "input"))
      (node (ref "U$2") (pin "33/A14") (pinfunction "33/A14/TX5_33/A14") (pintype "bidirectional"))
    )
    (net (code "100") (name "V31") (class "Default")
      (node (ref "IC5") (pin "7") (pinfunction "I7_7") (pintype "input"))
      (node (ref "U$2") (pin "34/A15") (pinfunction "34/A15/RX5_34/A15") (pintype "bidirectional"))
    )
    (net (code "101") (name "V32") (class "Default")
      (node (ref "IC5") (pin "8") (pinfunction "I8_8") (pintype "input"))
      (node (ref "U$2") (pin "35/A16") (pinfunction "35/A16/PWM_35/A16") (pintype "bidirectional"))
    )
    (net (code "102") (name "V33") (class "Default")
      (node (ref "IC6") (pin "1") (pinfunction "I1_1") (pintype "input"))
      (node (ref "U$2") (pin "38/A19") (pinfunction "38/A19/SDA1/PWM_38/A19") (pintype "bidirectional"))
    )
    (net (code "103") (name "V34") (class "Default")
      (node (ref "IC6") (pin "2") (pinfunction "I2_2") (pintype "input"))
      (node (ref "U$2") (pin "39/A20") (pinfunction "39/A20_39/A20") (pintype "bidirectional"))
    )
    (net (code "104") (name "V35") (class "Default")
      (node (ref "IC6") (pin "3") (pinfunction "I3_3") (pintype "input"))
      (node (ref "U$2") (pin "40") (pinfunction "40_40") (pintype "bidirectional"))
    )
    (net (code "105") (name "V36") (class "Default")
      (node (ref "IC6") (pin "4") (pinfunction "I4_4") (pintype "input"))
      (node (ref "U$2") (pin "41") (pinfunction "41_41") (pintype "bidirectional"))
    )
    (net (code "106") (name "V37") (class "Default")
      (node (ref "IC6") (pin "5") (pinfunction "I5_5") (pintype "input"))
      (node (ref "U$2") (pin "42") (pinfunction "42_42") (pintype "bidirectional"))
    )
    (net (code "107") (name "V38") (class "Default")
      (node (ref "IC6") (pin "6") (pinfunction "I6_6") (pintype "input"))
      (node (ref "U$2") (pin "43") (pinfunction "43_43") (pintype "bidirectional"))
    )
    (net (code "108") (name "V39") (class "Default")
      (node (ref "IC6") (pin "7") (pinfunction "I7_7") (pintype "input"))
      (node (ref "U$2") (pin "44") (pinfunction "MOSI2/44_44") (pintype "bidirectional"))
    )
    (net (code "109") (name "V40") (class "Default")
      (node (ref "IC6") (pin "8") (pinfunction "I8_8") (pintype "input"))
      (node (ref "U$2") (pin "45") (pinfunction "MISO2/45_45") (pintype "bidirectional"))
    )
    (net (code "110") (name "V41") (class "Default")
      (node (ref "IC8") (pin "1") (pinfunction "I1_1") (pintype "input"))
      (node (ref "U$2") (pin "46") (pinfunction "SCK2/46_46") (pintype "bidirectional"))
    )
    (net (code "111") (name "V42") (class "Default")
      (node (ref "IC8") (pin "2") (pinfunction "I2_2") (pintype "input"))
      (node (ref "U$2") (pin "47") (pinfunction "RX6/47_47") (pintype "bidirectional"))
    )
    (net (code "112") (name "V43") (class "Default")
      (node (ref "IC8") (pin "3") (pinfunction "I3_3") (pintype "input"))
      (node (ref "U$2") (pin "48") (pinfunction "TX6/48_48") (pintype "bidirectional"))
    )
    (net (code "113") (name "V44") (class "Default")
      (node (ref "IC8") (pin "4") (pinfunction "I4_4") (pintype "input"))
      (node (ref "U$2") (pin "49") (pinfunction "A23/49_49") (pintype "bidirectional"))
    )
    (net (code "114") (name "V45") (class "Default")
      (node (ref "IC8") (pin "5") (pinfunction "I5_5") (pintype "input"))
      (node (ref "U$2") (pin "50") (pinfunction "A24/50_50") (pintype "bidirectional"))
    )
    (net (code "115") (name "V46") (class "Default")
      (node (ref "IC8") (pin "6") (pinfunction "I6_6") (pintype "input"))
      (node (ref "U$2") (pin "51") (pinfunction "51_51") (pintype "bidirectional"))
    )
    (net (code "116") (name "V47") (class "Default")
      (node (ref "IC8") (pin "7") (pinfunction "I7_7") (pintype "input"))
      (node (ref "U$2") (pin "52") (pinfunction "52_52") (pintype "bidirectional"))
    )
    (net (code "117") (name "V48") (class "Default")
      (node (ref "IC8") (pin "8") (pinfunction "I8_8") (pintype "input"))
      (node (ref "U$2") (pin "53") (pinfunction "53_53") (pintype "bidirectional"))
    )
    (net (code "118") (name "V49") (class "Default")
      (node (ref "IC10") (pin "1") (pinfunction "I1_1") (pintype "input"))
      (node (ref "U$2") (pin "54") (pinfunction "54_54") (pintype "bidirectional"))
    )
    (net (code "119") (name "V50") (class "Default")
      (node (ref "IC10") (pin "2") (pinfunction "I2_2") (pintype "input"))
      (node (ref "U$2") (pin "55") (pinfunction "55_55") (pintype "bidirectional"))
    )
    (net (code "120") (name "V51") (class "Default")
      (node (ref "IC10") (pin "3") (pinfunction "I3_3") (pintype "input"))
      (node (ref "U$2") (pin "56") (pinfunction "56_56") (pintype "bidirectional"))
    )
    (net (code "121") (name "VBAT") (class "Default")
      (node (ref "U$2") (pin "VBAT") (pinfunction "VBAT_VBAT") (pintype "power_in"))
    )
    (net (code "122") (name "VUSB") (class "Default")
      (node (ref "U$2") (pin "VUSB") (pinfunction "VUSB_VUSB") (pintype "power_in"))
    )
    (net (code "123") (name "unconnected-(IC10-O4-Pad15)") (class "Default")
      (node (ref "IC10") (pin "15") (pinfunction "O4_15") (pintype "open_collector"))
    )
    (net (code "124") (name "unconnected-(IC10-O5-Pad14)") (class "Default")
      (node (ref "IC10") (pin "14") (pinfunction "O5_14") (pintype "open_collector"))
    )
    (net (code "125") (name "unconnected-(IC10-O6-Pad13)") (class "Default")
      (node (ref "IC10") (pin "13") (pinfunction "O6_13") (pintype "open_collector"))
    )
    (net (code "126") (name "unconnected-(SL1-Pad3)") (class "Default")
      (node (ref "SL1") (pin "3") (pinfunction "3_3") (pintype "passive"))
    )
    (net (code "127") (name "unconnected-(SL1-Pad6)") (class "Default")
      (node (ref "SL1") (pin "6") (pinfunction "6_6") (pintype "passive"))
    )
    (net (code "128") (name "unconnected-(U$2-A21{slash}DAC0-PadA21)") (class "Default")
      (node (ref "U$2") (pin "A21") (pinfunction "A21/DAC0_A21") (pintype "bidirectional"))
    )
    (net (code "129") (name "unconnected-(U$2-A22{slash}DAC1-PadA22)") (class "Default")
      (node (ref "U$2") (pin "A22") (pinfunction "A22/DAC1_A22") (pintype "bidirectional"))
    )
    (net (code "130") (name "unconnected-(U$2-Pad57)") (class "Default")
      (node (ref "U$2") (pin "57") (pinfunction "57_57") (pintype "bidirectional"))
    )
    (net (code "131") (name "unconnected-(U$2-PadA10)") (class "Default")
      (node (ref "U$2") (pin "A10") (pinfunction "A10_A10") (pintype "bidirectional"))
    )
    (net (code "132") (name "unconnected-(U$2-PadA11)") (class "Default")
      (node (ref "U$2") (pin "A11") (pinfunction "A11_A11") (pintype "bidirectional"))
    )
    (net (code "133") (name "unconnected-(U$2-PadA25)") (class "Default")
      (node (ref "U$2") (pin "A25") (pinfunction "A25_A25") (pintype "bidirectional"))
    )
    (net (code "134") (name "unconnected-(U$2-PadA26)") (class "Default")
      (node (ref "U$2") (pin "A26") (pinfunction "A26_A26") (pintype "bidirectional"))
    )
    (net (code "135") (name "unconnected-(U$2-PadDC)") (class "Default")
      (node (ref "U$2") (pin "DC") (pinfunction "DC_DC") (pintype "bidirectional"))
    )
    (net (code "136") (name "unconnected-(U$2-PadDE)") (class "Default")
      (node (ref "U$2") (pin "DE") (pinfunction "DE_DE") (pintype "bidirectional"))
    )
    (net (code "137") (name "unconnected-(U$2-PadDO)") (class "Default")
      (node (ref "U$2") (pin "DO") (pinfunction "DO_DO") (pintype "bidirectional"))
    )
    (net (code "138") (name "unconnected-(U$2-PadPGM)") (class "Default")
      (node (ref "U$2") (pin "PGM") (pinfunction "PGM_PGM") (pintype "bidirectional"))
    )
    (net (code "139") (name "unconnected-(U$2-PadRESET)") (class "Default")
      (node (ref "U$2") (pin "RESET") (pinfunction "RESET_RESET") (pintype "bidirectional"))
    )
    (net (code "140") (name "unconnected-(U$4-PadRING_SW)") (class "Default")
      (node (ref "U$4") (pin "RING_SW") (pinfunction "RING_SW_RING_SW") (pintype "bidirectional"))
    )
    (net (code "141") (name "unconnected-(U$7-Pad4)") (class "Default")
      (node (ref "U$7") (pin "4") (pinfunction "4_4") (pintype "passive"))
    )
    (net (code "142") (name "unconnected-(U$7-Pad7)") (class "Default")
      (node (ref "U$7") (pin "7") (pinfunction "7_7") (pintype "passive"))
    )
    (net (code "143") (name "unconnected-(U$7-Pad10)") (class "Default")
      (node (ref "U$7") (pin "10") (pinfunction "10_10") (pintype "passive"))
    )
    (net (code "144") (name "unconnected-(U$7-Pad13)") (class "Default")
      (node (ref "U$7") (pin "13") (pinfunction "13_13") (pintype "passive"))
    )
    (net (code "145") (name "unconnected-(U$7-Pad16)") (class "Default")
      (node (ref "U$7") (pin "16") (pinfunction "16_16") (pintype "passive"))
    )
    (net (code "146") (name "unconnected-(U$7-Pad19)") (class "Default")
      (node (ref "U$7") (pin "19") (pinfunction "19_19") (pintype "passive"))
    )
    (net (code "147") (name "unconnected-(U$7-Pad22)") (class "Default")
      (node (ref "U$7") (pin "22") (pinfunction "22_22") (pintype "passive"))
    )
    (net (code "148") (name "unconnected-(U$7-Pad25)") (class "Default")
      (node (ref "U$7") (pin "25") (pinfunction "25_25") (pintype "passive"))
    )
    (net (code "149") (name "unconnected-(U$8-Pad4)") (class "Default")
      (node (ref "U$8") (pin "4") (pinfunction "4_4") (pintype "passive"))
    )
    (net (code "150") (name "unconnected-(U$8-Pad7)") (class "Default")
      (node (ref "U$8") (pin "7") (pinfunction "7_7") (pintype "passive"))
    )
    (net (code "151") (name "unconnected-(U$8-Pad10)") (class "Default")
      (node (ref "U$8") (pin "10") (pinfunction "10_10") (pintype "passive"))
    )
    (net (code "152") (name "unconnected-(U$8-Pad13)") (class "Default")
      (node (ref "U$8") (pin "13") (pinfunction "13_13") (pintype "passive"))
    )
    (net (code "153") (name "unconnected-(U$8-Pad16)") (class "Default")
      (node (ref "U$8") (pin "16") (pinfunction "16_16") (pintype "passive"))
    )
    (net (code "154") (name "unconnected-(U$8-Pad19)") (class "Default")
      (node (ref "U$8") (pin "19") (pinfunction "19_19") (pintype "passive"))
    )
    (net (code "155") (name "unconnected-(U$8-Pad22)") (class "Default")
      (node (ref "U$8") (pin "22") (pinfunction "22_22") (pintype "passive"))
    )
    (net (code "156") (name "unconnected-(U$8-Pad25)") (class "Default")
      (node (ref "U$8") (pin "25") (pinfunction "25_25") (pintype "passive"))
    )
    (net (code "157") (name "unconnected-(U$9-Pad4)") (class "Default")
      (node (ref "U$9") (pin "4") (pinfunction "4_4") (pintype "passive"))
    )
    (net (code "158") (name "unconnected-(U$9-Pad7)") (class "Default")
      (node (ref "U$9") (pin "7") (pinfunction "7_7") (pintype "passive"))
    )
    (net (code "159") (name "unconnected-(U$9-Pad10)") (class "Default")
      (node (ref "U$9") (pin "10") (pinfunction "10_10") (pintype "passive"))
    )
    (net (code "160") (name "unconnected-(U$9-Pad13)") (class "Default")
      (node (ref "U$9") (pin "13") (pinfunction "13_13") (pintype "passive"))
    )
    (net (code "161") (name "unconnected-(U$9-Pad16)") (class "Default")
      (node (ref "U$9") (pin "16") (pinfunction "16_16") (pintype "passive"))
    )
    (net (code "162") (name "unconnected-(U$9-Pad19)") (class "Default")
      (node (ref "U$9") (pin "19") (pinfunction "19_19") (pintype "passive"))
    )
    (net (code "163") (name "unconnected-(U$9-Pad22)") (class "Default")
      (node (ref "U$9") (pin "22") (pinfunction "22_22") (pintype "passive"))
    )
    (net (code "164") (name "unconnected-(U$9-Pad25)") (class "Default")
      (node (ref "U$9") (pin "25") (pinfunction "25_25") (pintype "passive"))
    )
    (net (code "165") (name "unconnected-(U$14-Pad4)") (class "Default")
      (node (ref "U$14") (pin "4") (pinfunction "4_4") (pintype "passive"))
    )
    (net (code "166") (name "unconnected-(U$14-Pad7)") (class "Default")
      (node (ref "U$14") (pin "7") (pinfunction "7_7") (pintype "passive"))
    )
    (net (code "167") (name "unconnected-(U$14-Pad10)") (class "Default")
      (node (ref "U$14") (pin "10") (pinfunction "10_10") (pintype "passive"))
    )
    (net (code "168") (name "unconnected-(U$14-Pad13)") (class "Default")
      (node (ref "U$14") (pin "13") (pinfunction "13_13") (pintype "passive"))
    )
    (net (code "169") (name "unconnected-(U$14-Pad16)") (class "Default")
      (node (ref "U$14") (pin "16") (pinfunction "16_16") (pintype "passive"))
    )
    (net (code "170") (name "unconnected-(U$14-Pad19)") (class "Default")
      (node (ref "U$14") (pin "19") (pinfunction "19_19") (pintype "passive"))
    )
    (net (code "171") (name "unconnected-(U$14-Pad22)") (class "Default")
      (node (ref "U$14") (pin "22") (pinfunction "22_22") (pintype "passive"))
    )
    (net (code "172") (name "unconnected-(U$14-Pad25)") (class "Default")
      (node (ref "U$14") (pin "25") (pinfunction "25_25") (pintype "passive"))
    )
    (net (code "173") (name "unconnected-(U$15-Pad4)") (class "Default")
      (node (ref "U$15") (pin "4") (pinfunction "4_4") (pintype "passive"))
    )
    (net (code "174") (name "unconnected-(U$15-Pad7)") (class "Default")
      (node (ref "U$15") (pin "7") (pinfunction "7_7") (pintype "passive"))
    )
    (net (code "175") (name "unconnected-(U$15-Pad10)") (class "Default")
      (node (ref "U$15") (pin "10") (pinfunction "10_10") (pintype "passive"))
    )
    (net (code "176") (name "unconnected-(U$15-Pad13)") (class "Default")
      (node (ref "U$15") (pin "13") (pinfunction "13_13") (pintype "passive"))
    )
    (net (code "177") (name "unconnected-(U$15-Pad16)") (class "Default")
      (node (ref "U$15") (pin "16") (pinfunction "16_16") (pintype "passive"))
    )
    (net (code "178") (name "unconnected-(U$15-Pad19)") (class "Default")
      (node (ref "U$15") (pin "19") (pinfunction "19_19") (pintype "passive"))
    )
    (net (code "179") (name "unconnected-(U$15-Pad22)") (class "Default")
      (node (ref "U$15") (pin "22") (pinfunction "22_22") (pintype "passive"))
    )
    (net (code "180") (name "unconnected-(U$15-Pad25)") (class "Default")
      (node (ref "U$15") (pin "25") (pinfunction "25_25") (pintype "passive"))
    )
    (net (code "181") (name "unconnected-(U$17-Pad4)") (class "Default")
      (node (ref "U$17") (pin "4") (pinfunction "4_4") (pintype "passive"))
    )
    (net (code "182") (name "unconnected-(U$17-Pad7)") (class "Default")
      (node (ref "U$17") (pin "7") (pinfunction "7_7") (pintype "passive"))
    )
    (net (code "183") (name "unconnected-(U$17-Pad10)") (class "Default")
      (node (ref "U$17") (pin "10") (pinfunction "10_10") (pintype "passive"))
    )
    (net (code "184") (name "unconnected-(U$17-Pad13)") (class "Default")
      (node (ref "U$17") (pin "13") (pinfunction "13_13") (pintype "passive"))
    )
    (net (code "185") (name "unconnected-(U$17-Pad16)") (class "Default")
      (node (ref "U$17") (pin "16") (pinfunction "16_16") (pintype "passive"))
    )
    (net (code "186") (name "unconnected-(U$17-Pad19)") (class "Default")
      (node (ref "U$17") (pin "19") (pinfunction "19_19") (pintype "passive"))
    )
    (net (code "187") (name "unconnected-(U$17-Pad22)") (class "Default")
      (node (ref "U$17") (pin "22") (pinfunction "22_22") (pintype "passive"))
    )
    (net (code "188") (name "unconnected-(U$17-Pad25)") (class "Default")
      (node (ref "U$17") (pin "25") (pinfunction "25_25") (pintype "passive"))
    )
  )
)
